# observer.net
KiCad netlist of a schematic drawn in EAGLE
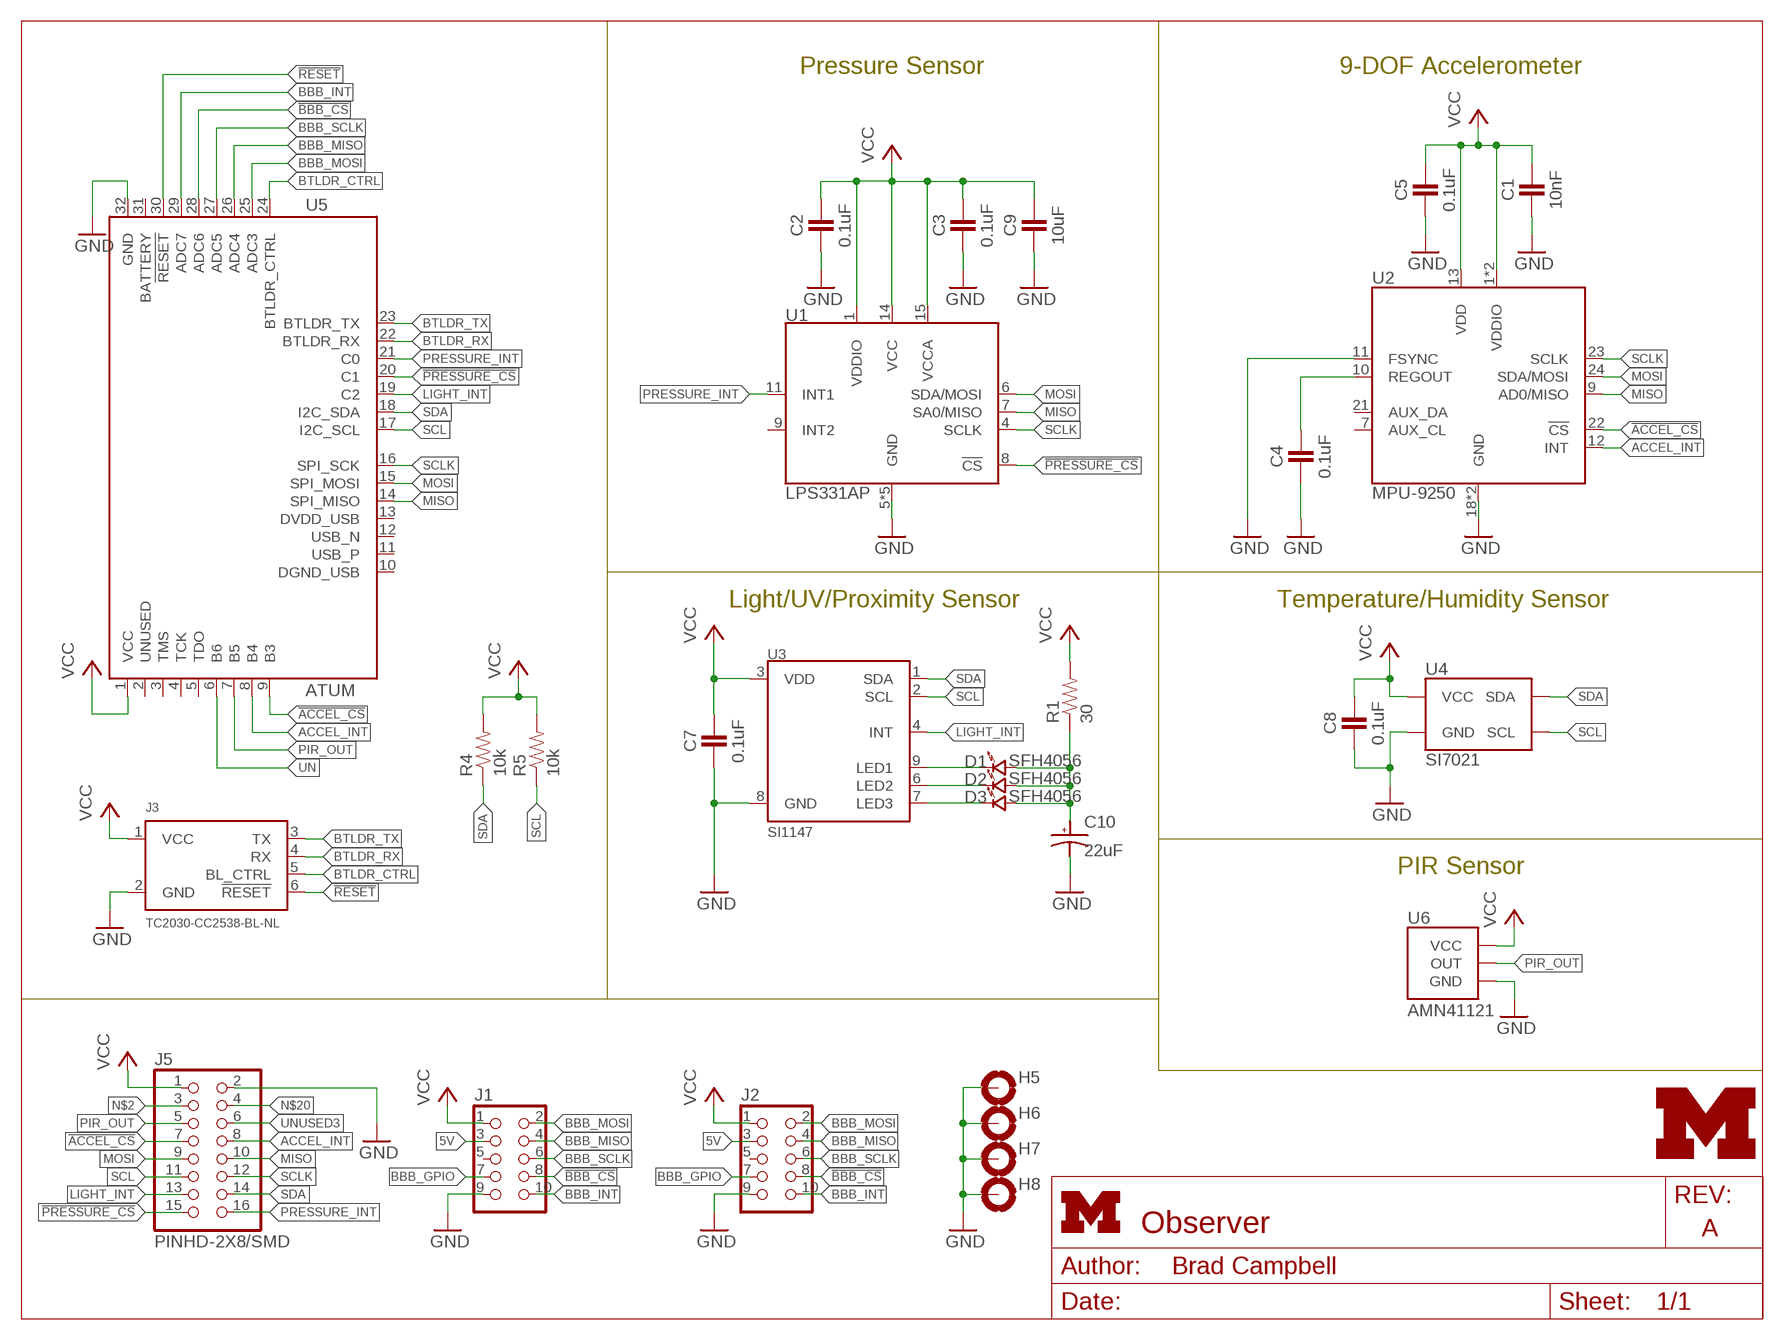
[diagram p0: schematic, sheet 1]

(export (version "E")
  (design (tool "Eeschema 10.0.6"))
  (components
    (comp (ref "C1")
      (value "10nF")
      (footprint "eagle-import:0402_CAP")
      (libsource (lib "eagle-import") (part "CAPACITOR"))
    )
    (comp (ref "C2")
      (value "0.1uF")
      (footprint "eagle-import:0402_CAP")
      (libsource (lib "eagle-import") (part "CAPACITOR"))
    )
    (comp (ref "C3")
      (value "0.1uF")
      (footprint "eagle-import:0402_CAP")
      (libsource (lib "eagle-import") (part "CAPACITOR"))
    )
    (comp (ref "C4")
      (value "0.1uF")
      (footprint "eagle-import:0402_CAP")
      (libsource (lib "eagle-import") (part "CAPACITOR"))
    )
    (comp (ref "C5")
      (value "0.1uF")
      (footprint "eagle-import:0402_CAP")
      (libsource (lib "eagle-import") (part "CAPACITOR"))
    )
    (comp (ref "C7")
      (value "0.1uF")
      (footprint "eagle-import:0402_CAP")
      (libsource (lib "eagle-import") (part "CAPACITOR"))
    )
    (comp (ref "C8")
      (value "0.1uF")
      (footprint "eagle-import:0402_CAP")
      (libsource (lib "eagle-import") (part "CAPACITOR"))
    )
    (comp (ref "C9")
      (value "10uF")
      (footprint "eagle-import:0402_CAP")
      (libsource (lib "eagle-import") (part "CAPACITOR"))
    )
    (comp (ref "C10")
      (value "22uF")
      (footprint "eagle-import:CAP0603")
      (libsource (lib "eagle-import") (part "CAP_POL0603"))
    )
    (comp (ref "D1")
      (value "SFH4056")
      (footprint "eagle-import:SFH4056")
      (libsource (lib "eagle-import") (part "SFH4056"))
    )
    (comp (ref "D2")
      (value "SFH4056")
      (footprint "eagle-import:SFH4056")
      (libsource (lib "eagle-import") (part "SFH4056"))
    )
    (comp (ref "D3")
      (value "SFH4056")
      (footprint "eagle-import:SFH4056")
      (libsource (lib "eagle-import") (part "SFH4056"))
    )
    (comp (ref "H5")
      (value "MOUNT-PAD-ROUND3.2")
      (footprint "eagle-import:3,2-PAD")
      (libsource (lib "eagle-import") (part "MOUNT-PAD-ROUND3.2"))
    )
    (comp (ref "H6")
      (value "MOUNT-PAD-ROUND3.2")
      (footprint "eagle-import:3,2-PAD")
      (libsource (lib "eagle-import") (part "MOUNT-PAD-ROUND3.2"))
    )
    (comp (ref "H7")
      (value "MOUNT-PAD-ROUND3.2")
      (footprint "eagle-import:3,2-PAD")
      (libsource (lib "eagle-import") (part "MOUNT-PAD-ROUND3.2"))
    )
    (comp (ref "H8")
      (value "MOUNT-PAD-ROUND3.2")
      (footprint "eagle-import:3,2-PAD")
      (libsource (lib "eagle-import") (part "MOUNT-PAD-ROUND3.2"))
    )
    (comp (ref "J1")
      (value "CON_HEADER_2X05-SMD+SHROUDED")
      (footprint "eagle-import:PINSHRD_SMT_2X05")
      (libsource (lib "eagle-import") (part "CON_HEADER_2X05-SMD+SHROUDED"))
    )
    (comp (ref "J2")
      (value "CON_HEADER_2X05-SMD+SHROUDED")
      (footprint "eagle-import:PINSHRD_SMT_2X05")
      (libsource (lib "eagle-import") (part "CON_HEADER_2X05-SMD+SHROUDED"))
    )
    (comp (ref "J3")
      (value "TC2030-CC2538-BL-NL")
      (footprint "eagle-import:TC2030-IDC-NL")
      (libsource (lib "eagle-import") (part "TC2030-CC2538-BL-NL"))
    )
    (comp (ref "J5")
      (value "PINHD-2X8/SMD")
      (footprint "eagle-import:2X8_SMD")
      (libsource (lib "eagle-import") (part "PINHD-2X8/SMD"))
    )
    (comp (ref "LOGO1")
      (value "UMICH_SOLID_TINY")
      (footprint "eagle-import:UMICH_SOLID_50MIL")
      (libsource (lib "eagle-import") (part "UMICH_SOLID_TINY"))
    )
    (comp (ref "R1")
      (value "30")
      (footprint "eagle-import:0402_RES")
      (libsource (lib "eagle-import") (part "RESISTOR0402_RES"))
    )
    (comp (ref "R4")
      (value "10k")
      (footprint "eagle-import:0402_RES")
      (libsource (lib "eagle-import") (part "RESISTOR0402_RES"))
    )
    (comp (ref "R5")
      (value "10k")
      (footprint "eagle-import:0402_RES")
      (libsource (lib "eagle-import") (part "RESISTOR0402_RES"))
    )
    (comp (ref "U1")
      (value "LPS331AP")
      (footprint "eagle-import:HCLGA-16_3MM")
      (libsource (lib "eagle-import") (part "LPS331AP"))
    )
    (comp (ref "U2")
      (value "MPU-9250")
      (footprint "eagle-import:QFN-24_3MM")
      (libsource (lib "eagle-import") (part "MPU-9250"))
    )
    (comp (ref "U3")
      (value "SI1147")
      (footprint "eagle-import:QFN-10_2MM")
      (libsource (lib "eagle-import") (part "SI1147"))
    )
    (comp (ref "U4")
      (value "SI7021")
      (footprint "eagle-import:DFN-6_3MM")
      (libsource (lib "eagle-import") (part "SI7021"))
    )
    (comp (ref "U5")
      (value "ATUM")
      (footprint "eagle-import:ATUM")
      (libsource (lib "eagle-import") (part "ATUM"))
    )
    (comp (ref "U6")
      (value "AMN41121")
      (footprint "eagle-import:AMN2")
      (libsource (lib "eagle-import") (part "AMN41121"))
    )
  )
  (nets
    (net (code "1") (name "/~{ACCEL_CS}") (class "Default")
      (node (ref "J5") (pin "7") (pinfunction "7_7") (pintype "passive"))
      (node (ref "U2") (pin "22") (pinfunction "~{CS}_22") (pintype "bidirectional"))
      (node (ref "U5") (pin "9") (pinfunction "B3_9") (pintype "bidirectional"))
    )
    (net (code "2") (name "/~{BBB_CS}") (class "Default")
      (node (ref "J1") (pin "8") (pinfunction "8_8") (pintype "passive"))
      (node (ref "J2") (pin "8") (pinfunction "8_8") (pintype "passive"))
      (node (ref "U5") (pin "28") (pinfunction "ADC6_28") (pintype "bidirectional"))
    )
    (net (code "3") (name "/~{PRESSURE_CS}") (class "Default")
      (node (ref "J5") (pin "15") (pinfunction "15_15") (pintype "passive"))
      (node (ref "U1") (pin "8") (pinfunction "~{CS}_8") (pintype "bidirectional"))
      (node (ref "U5") (pin "20") (pinfunction "C1_20") (pintype "bidirectional"))
    )
    (net (code "4") (name "/~{RESET}") (class "Default")
      (node (ref "J3") (pin "6") (pinfunction "~{RESET}_6") (pintype "bidirectional"))
      (node (ref "U5") (pin "30") (pinfunction "~{RESET}_30") (pintype "bidirectional"))
    )
    (net (code "5") (name "5V") (class "Default")
      (node (ref "J1") (pin "3") (pinfunction "3_3") (pintype "passive"))
      (node (ref "J2") (pin "3") (pinfunction "3_3") (pintype "passive"))
    )
    (net (code "6") (name "ACCEL_INT") (class "Default")
      (node (ref "J5") (pin "8") (pinfunction "8_8") (pintype "passive"))
      (node (ref "U2") (pin "12") (pinfunction "INT_12") (pintype "bidirectional"))
      (node (ref "U5") (pin "8") (pinfunction "B4_8") (pintype "bidirectional"))
    )
    (net (code "7") (name "BBB_GPIO") (class "Default")
      (node (ref "J1") (pin "7") (pinfunction "7_7") (pintype "passive"))
      (node (ref "J2") (pin "7") (pinfunction "7_7") (pintype "passive"))
    )
    (net (code "8") (name "BBB_INT") (class "Default")
      (node (ref "J1") (pin "10") (pinfunction "10_10") (pintype "passive"))
      (node (ref "J2") (pin "10") (pinfunction "10_10") (pintype "passive"))
      (node (ref "U5") (pin "29") (pinfunction "ADC7_29") (pintype "bidirectional"))
    )
    (net (code "9") (name "BBB_MISO") (class "Default")
      (node (ref "J1") (pin "4") (pinfunction "4_4") (pintype "passive"))
      (node (ref "J2") (pin "4") (pinfunction "4_4") (pintype "passive"))
      (node (ref "U5") (pin "26") (pinfunction "ADC4_26") (pintype "bidirectional"))
    )
    (net (code "10") (name "BBB_MOSI") (class "Default")
      (node (ref "J1") (pin "2") (pinfunction "2_2") (pintype "passive"))
      (node (ref "J2") (pin "2") (pinfunction "2_2") (pintype "passive"))
      (node (ref "U5") (pin "25") (pinfunction "ADC3_25") (pintype "bidirectional"))
    )
    (net (code "11") (name "BBB_SCLK") (class "Default")
      (node (ref "J1") (pin "6") (pinfunction "6_6") (pintype "passive"))
      (node (ref "J2") (pin "6") (pinfunction "6_6") (pintype "passive"))
      (node (ref "U5") (pin "27") (pinfunction "ADC5_27") (pintype "bidirectional"))
    )
    (net (code "12") (name "BTLDR_CTRL") (class "Default")
      (node (ref "J3") (pin "5") (pinfunction "BL_CTRL_5") (pintype "bidirectional"))
      (node (ref "U5") (pin "24") (pinfunction "BTLDR_CTRL_24") (pintype "bidirectional"))
    )
    (net (code "13") (name "BTLDR_RX") (class "Default")
      (node (ref "J3") (pin "4") (pinfunction "RX_4") (pintype "bidirectional"))
      (node (ref "U5") (pin "22") (pinfunction "BTLDR_RX_22") (pintype "bidirectional"))
    )
    (net (code "14") (name "BTLDR_TX") (class "Default")
      (node (ref "J3") (pin "3") (pinfunction "TX_3") (pintype "bidirectional"))
      (node (ref "U5") (pin "23") (pinfunction "BTLDR_TX_23") (pintype "bidirectional"))
    )
    (net (code "15") (name "GND") (class "Default")
      (node (ref "C1") (pin "2") (pinfunction "2_2") (pintype "bidirectional"))
      (node (ref "C10") (pin "NEG") (pinfunction "ANODE_NEG") (pintype "bidirectional"))
      (node (ref "C2") (pin "2") (pinfunction "2_2") (pintype "bidirectional"))
      (node (ref "C3") (pin "2") (pinfunction "2_2") (pintype "bidirectional"))
      (node (ref "C4") (pin "2") (pinfunction "2_2") (pintype "bidirectional"))
      (node (ref "C5") (pin "2") (pinfunction "2_2") (pintype "bidirectional"))
      (node (ref "C7") (pin "2") (pinfunction "2_2") (pintype "bidirectional"))
      (node (ref "C8") (pin "2") (pinfunction "2_2") (pintype "bidirectional"))
      (node (ref "C9") (pin "2") (pinfunction "2_2") (pintype "bidirectional"))
      (node (ref "H5") (pin "B3,2") (pinfunction "MOUNT_B3,2") (pintype "passive"))
      (node (ref "H6") (pin "B3,2") (pinfunction "MOUNT_B3,2") (pintype "passive"))
      (node (ref "H7") (pin "B3,2") (pinfunction "MOUNT_B3,2") (pintype "passive"))
      (node (ref "H8") (pin "B3,2") (pinfunction "MOUNT_B3,2") (pintype "passive"))
      (node (ref "J1") (pin "9") (pinfunction "9_9") (pintype "passive"))
      (node (ref "J2") (pin "9") (pinfunction "9_9") (pintype "passive"))
      (node (ref "J3") (pin "2") (pinfunction "GND_2") (pintype "bidirectional"))
      (node (ref "J5") (pin "2") (pinfunction "2_2") (pintype "passive"))
      (node (ref "U1") (pin "10") (pinfunction "GND_10") (pintype "bidirectional"))
      (node (ref "U1") (pin "12") (pinfunction "GND_12") (pintype "bidirectional"))
      (node (ref "U1") (pin "13") (pinfunction "GND_13") (pintype "bidirectional"))
      (node (ref "U1") (pin "16") (pinfunction "GND_16") (pintype "bidirectional"))
      (node (ref "U1") (pin "5") (pinfunction "GND_5") (pintype "bidirectional"))
      (node (ref "U2") (pin "11") (pinfunction "FSYNC_11") (pintype "bidirectional"))
      (node (ref "U2") (pin "18") (pinfunction "GND_18") (pintype "bidirectional"))
      (node (ref "U2") (pin "20") (pinfunction "GND_20") (pintype "bidirectional"))
      (node (ref "U3") (pin "8") (pinfunction "GND_8") (pintype "bidirectional"))
      (node (ref "U4") (pin "2") (pinfunction "GND_2") (pintype "bidirectional"))
      (node (ref "U5") (pin "32") (pinfunction "GND_32") (pintype "bidirectional"))
      (node (ref "U6") (pin "GND") (pinfunction "GND_GND") (pintype "bidirectional"))
    )
    (net (code "16") (name "LIGHT_INT") (class "Default")
      (node (ref "J5") (pin "13") (pinfunction "13_13") (pintype "passive"))
      (node (ref "U3") (pin "4") (pinfunction "INT_4") (pintype "bidirectional"))
      (node (ref "U5") (pin "19") (pinfunction "C2_19") (pintype "bidirectional"))
    )
    (net (code "17") (name "MISO") (class "Default")
      (node (ref "J5") (pin "10") (pinfunction "10_10") (pintype "passive"))
      (node (ref "U1") (pin "7") (pinfunction "SA0/MISO_7") (pintype "bidirectional"))
      (node (ref "U2") (pin "9") (pinfunction "AD0/MISO_9") (pintype "bidirectional"))
      (node (ref "U5") (pin "14") (pinfunction "SPI_MISO_14") (pintype "bidirectional"))
    )
    (net (code "18") (name "MOSI") (class "Default")
      (node (ref "J5") (pin "9") (pinfunction "9_9") (pintype "passive"))
      (node (ref "U1") (pin "6") (pinfunction "SDA/MOSI_6") (pintype "bidirectional"))
      (node (ref "U2") (pin "24") (pinfunction "SDA/MOSI_24") (pintype "bidirectional"))
      (node (ref "U5") (pin "15") (pinfunction "SPI_MOSI_15") (pintype "bidirectional"))
    )
    (net (code "19") (name "N$2") (class "Default")
      (node (ref "J5") (pin "3") (pinfunction "3_3") (pintype "passive"))
    )
    (net (code "20") (name "N$20") (class "Default")
      (node (ref "J5") (pin "4") (pinfunction "4_4") (pintype "passive"))
    )
    (net (code "21") (name "Net-(C10-CATHODE)") (class "Default")
      (node (ref "C10") (pin "POS") (pinfunction "CATHODE_POS") (pintype "bidirectional"))
      (node (ref "D1") (pin "ANODE") (pinfunction "ANODE_ANODE") (pintype "bidirectional"))
      (node (ref "D2") (pin "ANODE") (pinfunction "ANODE_ANODE") (pintype "bidirectional"))
      (node (ref "D3") (pin "ANODE") (pinfunction "ANODE_ANODE") (pintype "bidirectional"))
      (node (ref "R1") (pin "1") (pinfunction "1_1") (pintype "passive"))
    )
    (net (code "22") (name "Net-(U2-REGOUT)") (class "Default")
      (node (ref "C4") (pin "1") (pinfunction "1_1") (pintype "bidirectional"))
      (node (ref "U2") (pin "10") (pinfunction "REGOUT_10") (pintype "bidirectional"))
    )
    (net (code "23") (name "Net-(U3-LED1)") (class "Default")
      (node (ref "D1") (pin "CATHODE") (pinfunction "CATHODE_CATHODE") (pintype "bidirectional"))
      (node (ref "U3") (pin "9") (pinfunction "LED1_9") (pintype "bidirectional"))
    )
    (net (code "24") (name "Net-(U3-LED2)") (class "Default")
      (node (ref "D2") (pin "CATHODE") (pinfunction "CATHODE_CATHODE") (pintype "bidirectional"))
      (node (ref "U3") (pin "6") (pinfunction "LED2_6") (pintype "bidirectional"))
    )
    (net (code "25") (name "Net-(U3-LED3)") (class "Default")
      (node (ref "D3") (pin "CATHODE") (pinfunction "CATHODE_CATHODE") (pintype "bidirectional"))
      (node (ref "U3") (pin "7") (pinfunction "LED3_7") (pintype "bidirectional"))
    )
    (net (code "26") (name "PIR_OUT") (class "Default")
      (node (ref "J5") (pin "5") (pinfunction "5_5") (pintype "passive"))
      (node (ref "U5") (pin "7") (pinfunction "B5_7") (pintype "bidirectional"))
      (node (ref "U6") (pin "OUT") (pinfunction "OUT_OUT") (pintype "bidirectional"))
    )
    (net (code "27") (name "PRESSURE_INT") (class "Default")
      (node (ref "J5") (pin "16") (pinfunction "16_16") (pintype "passive"))
      (node (ref "U1") (pin "11") (pinfunction "INT1_11") (pintype "bidirectional"))
      (node (ref "U5") (pin "21") (pinfunction "C0_21") (pintype "bidirectional"))
    )
    (net (code "28") (name "SCL") (class "Default")
      (node (ref "J5") (pin "11") (pinfunction "11_11") (pintype "passive"))
      (node (ref "R5") (pin "1") (pinfunction "1_1") (pintype "passive"))
      (node (ref "U3") (pin "2") (pinfunction "SCL_2") (pintype "bidirectional"))
      (node (ref "U4") (pin "6") (pinfunction "SCL_6") (pintype "bidirectional"))
      (node (ref "U5") (pin "17") (pinfunction "I2C_SCL_17") (pintype "bidirectional"))
    )
    (net (code "29") (name "SCLK") (class "Default")
      (node (ref "J5") (pin "12") (pinfunction "12_12") (pintype "passive"))
      (node (ref "U1") (pin "4") (pinfunction "SCLK_4") (pintype "bidirectional"))
      (node (ref "U2") (pin "23") (pinfunction "SCLK_23") (pintype "bidirectional"))
      (node (ref "U5") (pin "16") (pinfunction "SPI_SCK_16") (pintype "bidirectional"))
    )
    (net (code "30") (name "SDA") (class "Default")
      (node (ref "J5") (pin "14") (pinfunction "14_14") (pintype "passive"))
      (node (ref "R4") (pin "1") (pinfunction "1_1") (pintype "passive"))
      (node (ref "U3") (pin "1") (pinfunction "SDA_1") (pintype "bidirectional"))
      (node (ref "U4") (pin "1") (pinfunction "SDA_1") (pintype "bidirectional"))
      (node (ref "U5") (pin "18") (pinfunction "I2C_SDA_18") (pintype "bidirectional"))
    )
    (net (code "31") (name "UN") (class "Default")
      (node (ref "U5") (pin "6") (pinfunction "B6_6") (pintype "bidirectional"))
    )
    (net (code "32") (name "UNUSED3") (class "Default")
      (node (ref "J5") (pin "6") (pinfunction "6_6") (pintype "passive"))
    )
    (net (code "33") (name "VCC") (class "Default")
      (node (ref "C1") (pin "1") (pinfunction "1_1") (pintype "bidirectional"))
      (node (ref "C2") (pin "1") (pinfunction "1_1") (pintype "bidirectional"))
      (node (ref "C3") (pin "1") (pinfunction "1_1") (pintype "bidirectional"))
      (node (ref "C5") (pin "1") (pinfunction "1_1") (pintype "bidirectional"))
      (node (ref "C7") (pin "1") (pinfunction "1_1") (pintype "bidirectional"))
      (node (ref "C8") (pin "1") (pinfunction "1_1") (pintype "bidirectional"))
      (node (ref "C9") (pin "1") (pinfunction "1_1") (pintype "bidirectional"))
      (node (ref "J1") (pin "1") (pinfunction "1_1") (pintype "passive"))
      (node (ref "J2") (pin "1") (pinfunction "1_1") (pintype "passive"))
      (node (ref "J3") (pin "1") (pinfunction "VCC_1") (pintype "bidirectional"))
      (node (ref "J5") (pin "1") (pinfunction "1_1") (pintype "passive"))
      (node (ref "R1") (pin "2") (pinfunction "2_2") (pintype "passive"))
      (node (ref "R4") (pin "2") (pinfunction "2_2") (pintype "passive"))
      (node (ref "R5") (pin "2") (pinfunction "2_2") (pintype "passive"))
      (node (ref "U1") (pin "1") (pinfunction "VDDIO_1") (pintype "bidirectional"))
      (node (ref "U1") (pin "14") (pinfunction "VCC_14") (pintype "bidirectional"))
      (node (ref "U1") (pin "15") (pinfunction "VCCA_15") (pintype "bidirectional"))
      (node (ref "U2") (pin "1") (pinfunction "VDDIO_1") (pintype "bidirectional"))
      (node (ref "U2") (pin "13") (pinfunction "VDD_13") (pintype "bidirectional"))
      (node (ref "U2") (pin "8") (pinfunction "VDDIO_8") (pintype "bidirectional"))
      (node (ref "U3") (pin "3") (pinfunction "VDD_3") (pintype "bidirectional"))
      (node (ref "U4") (pin "5") (pinfunction "VCC_5") (pintype "bidirectional"))
      (node (ref "U5") (pin "1") (pinfunction "VCC_1") (pintype "bidirectional"))
      (node (ref "U6") (pin "VCC") (pinfunction "VCC_VCC") (pintype "bidirectional"))
    )
    (net (code "34") (name "unconnected-(J1-Pad5)") (class "Default")
      (node (ref "J1") (pin "5") (pinfunction "5_5") (pintype "passive"))
    )
    (net (code "35") (name "unconnected-(J2-Pad5)") (class "Default")
      (node (ref "J2") (pin "5") (pinfunction "5_5") (pintype "passive"))
    )
    (net (code "36") (name "unconnected-(U1-INT2-Pad9)") (class "Default")
      (node (ref "U1") (pin "9") (pinfunction "INT2_9") (pintype "bidirectional"))
    )
    (net (code "37") (name "unconnected-(U2-AUX_CL-Pad7)") (class "Default")
      (node (ref "U2") (pin "7") (pinfunction "AUX_CL_7") (pintype "bidirectional"))
    )
    (net (code "38") (name "unconnected-(U2-AUX_DA-Pad21)") (class "Default")
      (node (ref "U2") (pin "21") (pinfunction "AUX_DA_21") (pintype "bidirectional"))
    )
    (net (code "39") (name "unconnected-(U5-BATTERY-Pad31)") (class "Default")
      (node (ref "U5") (pin "31") (pinfunction "BATTERY_31") (pintype "bidirectional"))
    )
    (net (code "40") (name "unconnected-(U5-DGND_USB-Pad10)") (class "Default")
      (node (ref "U5") (pin "10") (pinfunction "DGND_USB_10") (pintype "bidirectional"))
    )
    (net (code "41") (name "unconnected-(U5-DVDD_USB-Pad13)") (class "Default")
      (node (ref "U5") (pin "13") (pinfunction "DVDD_USB_13") (pintype "bidirectional"))
    )
    (net (code "42") (name "unconnected-(U5-TCK-Pad4)") (class "Default")
      (node (ref "U5") (pin "4") (pinfunction "TCK_4") (pintype "bidirectional"))
    )
    (net (code "43") (name "unconnected-(U5-TDO-Pad5)") (class "Default")
      (node (ref "U5") (pin "5") (pinfunction "TDO_5") (pintype "bidirectional"))
    )
    (net (code "44") (name "unconnected-(U5-TMS-Pad3)") (class "Default")
      (node (ref "U5") (pin "3") (pinfunction "TMS_3") (pintype "bidirectional"))
    )
    (net (code "45") (name "unconnected-(U5-UNUSED-Pad2)") (class "Default")
      (node (ref "U5") (pin "2") (pinfunction "UNUSED_2") (pintype "bidirectional"))
    )
    (net (code "46") (name "unconnected-(U5-USB_N-Pad12)") (class "Default")
      (node (ref "U5") (pin "12") (pinfunction "USB_N_12") (pintype "bidirectional"))
    )
    (net (code "47") (name "unconnected-(U5-USB_P-Pad11)") (class "Default")
      (node (ref "U5") (pin "11") (pinfunction "USB_P_11") (pintype "bidirectional"))
    )
  )
)
